# AD9837MagPhase.net
KiCad netlist of a schematic drawn in Altium Designer
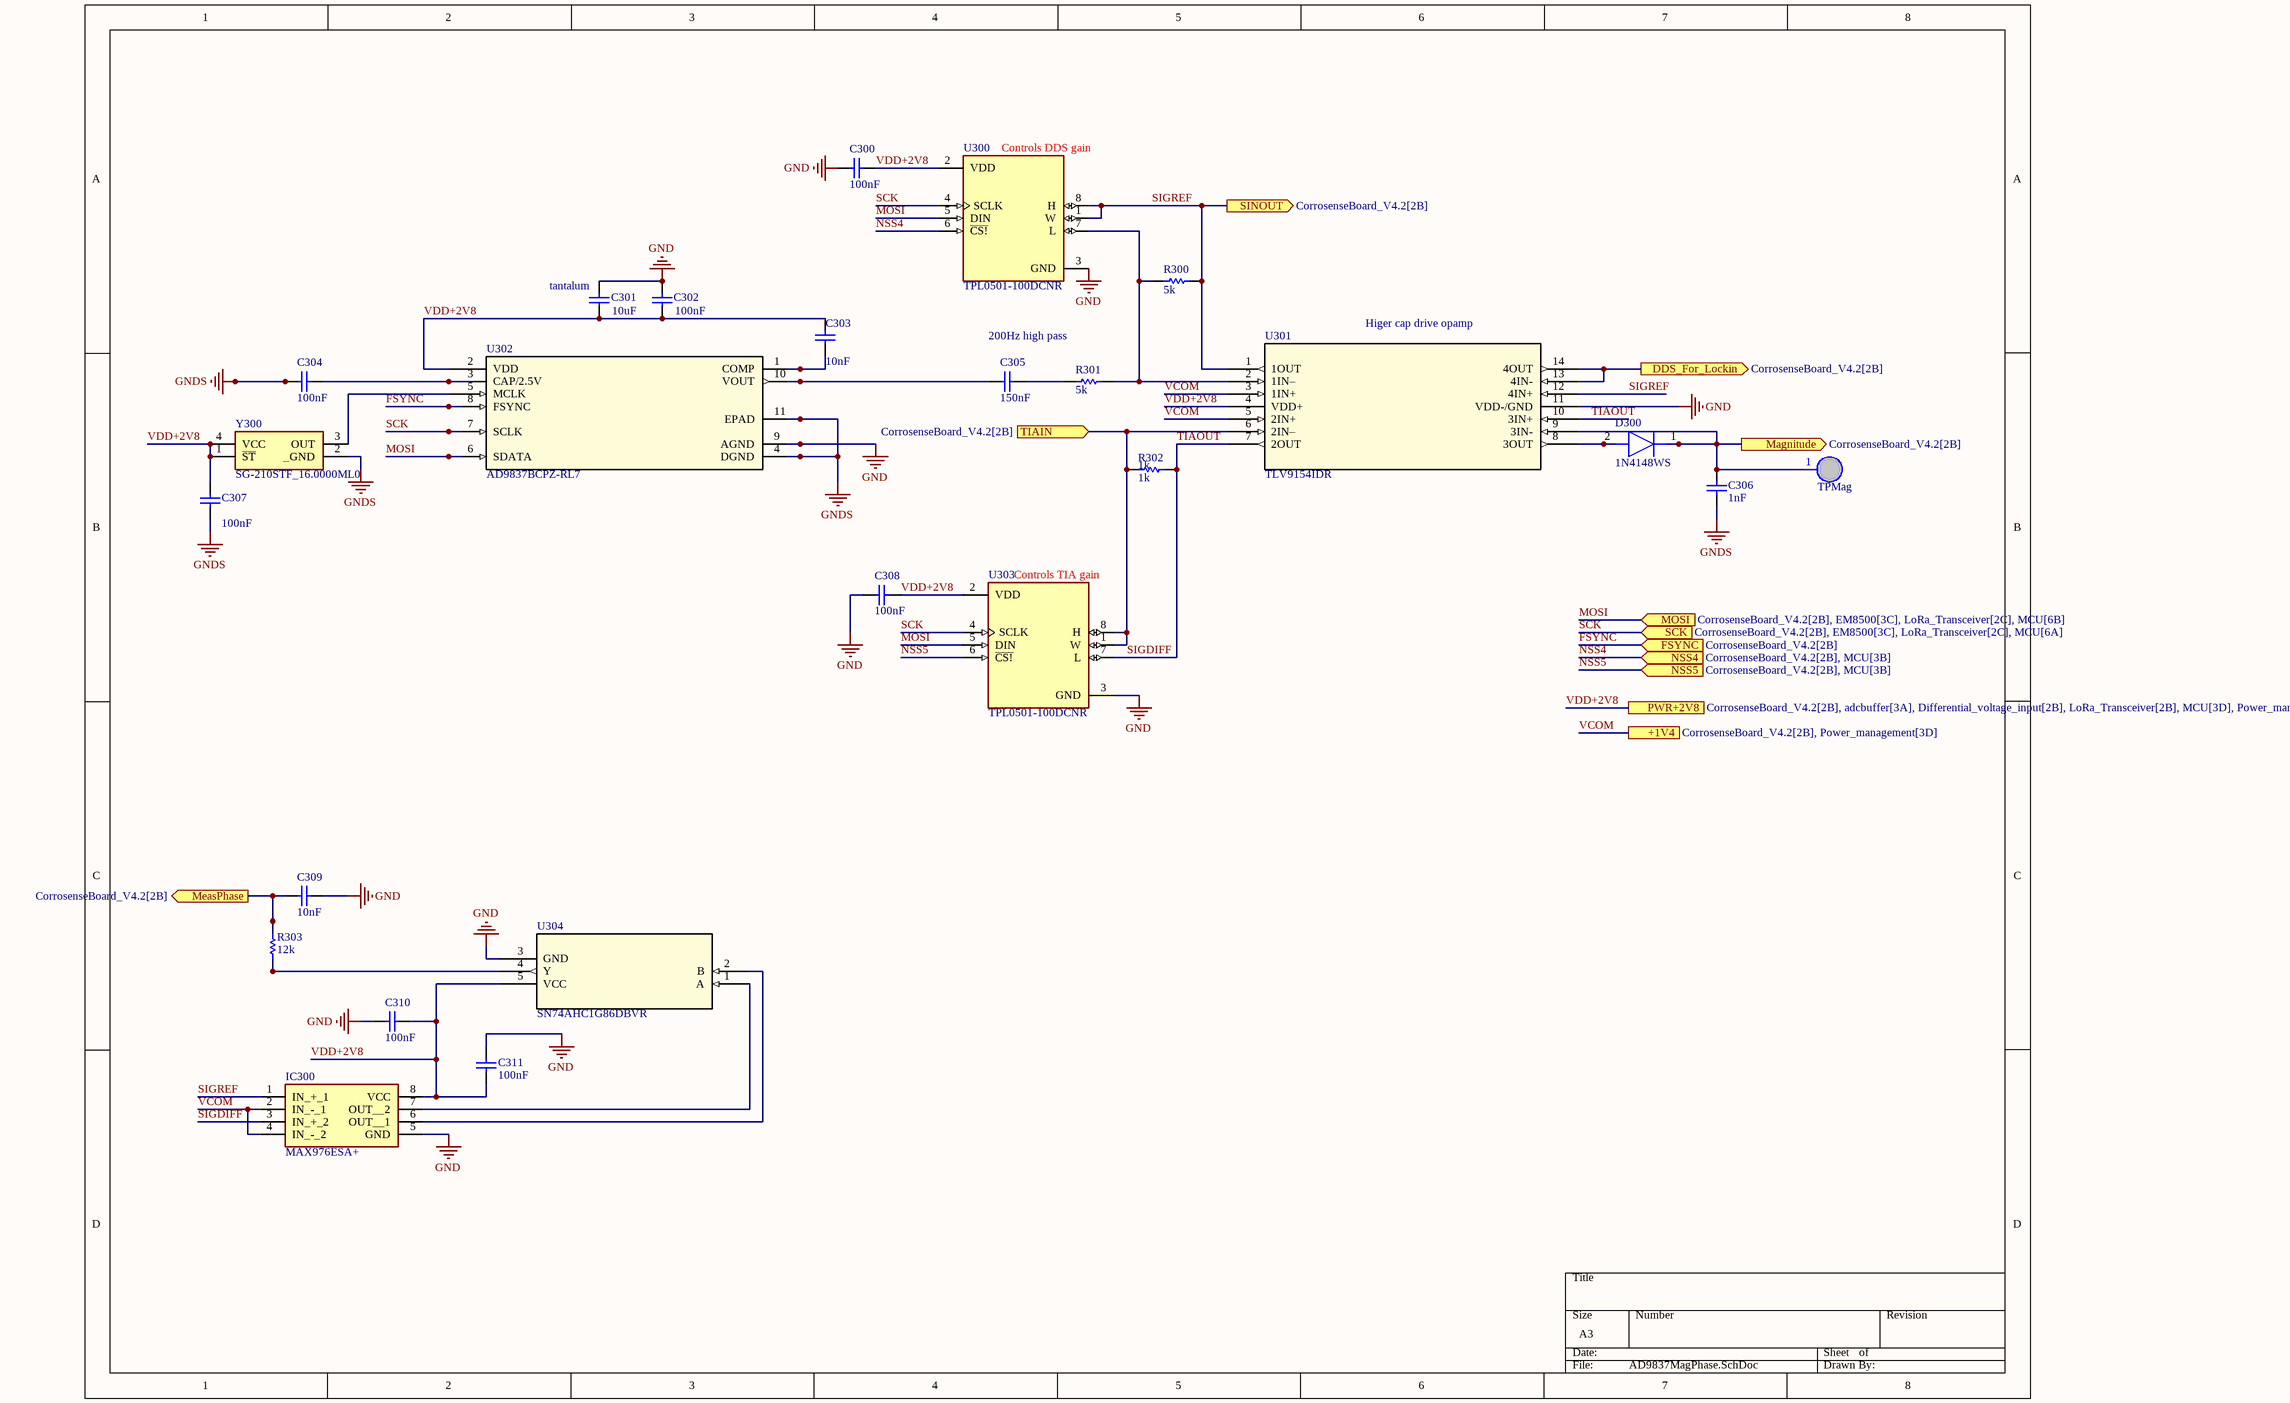
[diagram p0: AD9837MagPhase.SchDoc]

(export (version "E")
  (design (tool "Eeschema 10.0.6"))
  (components
    (comp (ref "C300")
      (value "100nF")
      (footprint "1608[0603]")
      (description "CAP CER 25V X7R 0603")
      (fields (field (name "TOLERANCE") "±10%") (field (name "MANUFACTURER") "Murata Electronics"))
      (libsource (lib "Miscellaneous Devices") (part "Cap"))
    )
    (comp (ref "C301")
      (value "10uF")
      (footprint "1608[0603]")
      (description "CAP CER 25V X7R 0603")
      (fields (field (name "TOLERANCE") "±20%") (field (name "MANUFACTURER") "Vishay / Sprague"))
      (libsource (lib "Miscellaneous Devices") (part "Cap"))
    )
    (comp (ref "C302")
      (value "100nF")
      (footprint "1608[0603]")
      (description "CAP CER 25V X7R 0603")
      (fields (field (name "TOLERANCE") "±10%") (field (name "MANUFACTURER") "Murata Electronics"))
      (libsource (lib "Miscellaneous Devices") (part "Cap"))
    )
    (comp (ref "C303")
      (value "10nF")
      (footprint "1608[0603]")
      (description "CAP CER 25V X7R 0603")
      (fields (field (name "TOLERANCE") "±10%") (field (name "MANUFACTURER") "Murata Electronics"))
      (libsource (lib "Miscellaneous Devices") (part "Cap"))
    )
    (comp (ref "C304")
      (value "100nF")
      (footprint "1608[0603]")
      (description "CAP CER 25V X7R 0603")
      (fields (field (name "TOLERANCE") "±10%") (field (name "MANUFACTURER") "Murata Electronics"))
      (libsource (lib "Miscellaneous Devices") (part "Cap"))
    )
    (comp (ref "C305")
      (value "150nF")
      (footprint "1608[0603]")
      (description "CAP CER 25V X7R 0603")
      (fields (field (name "TOLERANCE") "±10%") (field (name "MANUFACTURER") "Murata Electronics"))
      (libsource (lib "Miscellaneous Devices") (part "Cap"))
    )
    (comp (ref "C306")
      (value "1nF")
      (footprint "1608[0603]")
      (description "CAP CER 25V X7R 0603")
      (fields (field (name "TOLERANCE") "±10%") (field (name "MANUFACTURER") "KYOCERA AVX"))
      (libsource (lib "Miscellaneous Devices") (part "Cap"))
    )
    (comp (ref "C307")
      (value "100nF")
      (footprint "1608[0603]")
      (description "CAP CER 25V X7R 0603")
      (fields (field (name "TOLERANCE") "±10%") (field (name "MANUFACTURER") "Murata Electronics"))
      (libsource (lib "Miscellaneous Devices") (part "Cap"))
    )
    (comp (ref "C308")
      (value "100nF")
      (footprint "1608[0603]")
      (description "CAP CER 25V X7R 0603")
      (fields (field (name "TOLERANCE") "±10%") (field (name "MANUFACTURER") "Murata Electronics"))
      (libsource (lib "Miscellaneous Devices") (part "Cap"))
    )
    (comp (ref "C309")
      (value "10nF")
      (footprint "1608[0603]")
      (description "CAP CER 25V X7R 0603")
      (fields (field (name "TOLERANCE") "±10%") (field (name "MANUFACTURER") "Murata Electronics"))
      (libsource (lib "Miscellaneous Devices") (part "Cap"))
    )
    (comp (ref "C310")
      (value "100nF")
      (footprint "1608[0603]")
      (description "CAP CER 25V X7R 0603")
      (fields (field (name "TOLERANCE") "±10%") (field (name "MANUFACTURER") "Murata Electronics"))
      (libsource (lib "Miscellaneous Devices") (part "Cap"))
    )
    (comp (ref "C311")
      (value "100nF")
      (footprint "1608[0603]")
      (description "CAP CER 25V X7R 0603")
      (fields (field (name "TOLERANCE") "±10%") (field (name "MANUFACTURER") "Murata Electronics"))
      (libsource (lib "Miscellaneous Devices") (part "Cap"))
    )
    (comp (ref "D300")
      (value "1N4148WS")
      (footprint "SamacSys:SOD2513X100N")
      (description "Diode")
      (fields
        (field (name "MOUSER PART NUMBER") "821-1N4148WS")
        (field (name "MANUFACTURER") "Taiwan Semiconductor")
      )
      (libsource (lib "*") (part "1N4148WS"))
    )
    (comp (ref "IC300")
      (value "MAX976ESA+")
      (footprint "SOIC127P600X175-8N")
      (description "Integrated Circuit")
      (fields
        (field (name "MOUSER PART NUMBER") "700-MAX976ESA")
        (field (name "MANUFACTURER") "Analog Devices")
      )
      (libsource (lib "*") (part "MAX976ESA+"))
    )
    (comp (ref "R300")
      (value "5k")
      (footprint "1608[0603]")
      (description "RES SMD 2% 1.5W 0603")
      (fields
        (field (name "MP") "-65°C ~ 155°C")
        (field (name "TOLERANCE") "2%")
        (field (name "PUBLISHER") "Altium Limited")
      )
      (libsource (lib "Res1") (part "Res1"))
    )
    (comp (ref "R301")
      (value "5k")
      (footprint "1608[0603]")
      (description "RES SMD 2% 1.5W 0603")
      (fields
        (field (name "MP") "-65°C ~ 155°C")
        (field (name "TOLERANCE") "2%")
        (field (name "PUBLISHER") "Altium Limited")
      )
      (libsource (lib "Res1") (part "Res1"))
    )
    (comp (ref "R302")
      (value "1k")
      (footprint "1608[0603]")
      (description "RES SMD 2% 1.5W 0603")
      (fields
        (field (name "ALTIUM_VALUE") "1k")
        (field (name "MP") "-65°C ~ 155°C")
        (field (name "TOLERANCE") "2%")
        (field (name "PUBLISHER") "Altium Limited")
      )
      (libsource (lib "Res1") (part "Res1"))
    )
    (comp (ref "R303")
      (value "12k")
      (footprint "1608[0603]")
      (description "RES SMD 2% 1.5W 0603")
      (fields
        (field (name "MP") "-65°C ~ 155°C")
        (field (name "TOLERANCE") "2%")
        (field (name "PUBLISHER") "Altium Limited")
      )
      (libsource (lib "Res1") (part "Res1"))
    )
    (comp (ref "TPMag") (value "TP") (footprint "PCBComponent_1") (libsource (lib "TP") (part "TP")))
    (comp (ref "U300")
      (value "TPL0501-100DCNR")
      (footprint "SOT65P280X145-8N")
      (description "256-Taps, 100k, Single-Channel Potentiometer With SPI Interface 8-SOT-23 -40 to 125")
      (fields (field (name "MANUFACTURER") "Texas Instruments"))
      (libsource (lib "TPL0501-100DCNR") (part "TPL0501-100DCNR"))
    )
    (comp (ref "U301")
      (value "TLV9154IDR")
      (footprint "SOIC127P600X175-14N")
      (description "No Description Available")
      (fields (field (name "MANUFACTURER") "Texas Instruments"))
      (libsource (lib "TLV2444CD") (part "TLV2444CD"))
    )
    (comp (ref "U302")
      (value "AD9837BCPZ-RL7")
      (footprint "CP_10_9_ADI")
      (description "No Description Available")
      (fields (field (name "MANUFACTURER") "Analog Devices"))
      (libsource (lib "AD9837ACPZ-RL7") (part "AD9837ACPZ-RL7"))
    )
    (comp (ref "U303")
      (value "TPL0501-100DCNR")
      (footprint "SOT65P280X145-8N")
      (description "256-Taps, 100k, Single-Channel Potentiometer With SPI Interface 8-SOT-23 -40 to 125")
      (fields (field (name "MANUFACTURER") "Texas Instruments"))
      (libsource (lib "TPL0501-100DCNR") (part "TPL0501-100DCNR"))
    )
    (comp (ref "U304")
      (value "SN74AHC1G86DBVR")
      (footprint "SOT95P280X145-5N")
      (description "No Description Available")
      (fields (field (name "MANUFACTURER") "Texas Instruments"))
      (libsource (lib "SN74AHC1G86DBVR") (part "SN74AHC1G86DBVR"))
    )
    (comp (ref "Y300")
      (value "SG-210STF_16.0000ML0")
      (footprint "SG210STF160000ML0")
      (description "Crystal or Oscillator")
      (fields
        (field (name "MANUFACTURER_PART_NUMBER") "SG-210STF 16.0000ML0")
        (field (name "MOUSER PART NUMBER") "732-SG-210STF16ML0")
      )
      (libsource (lib "*") (part "SG-210STF_16.0000ML0"))
    )
  )
  (nets
    (net (code "1") (name "/DDS_For_Lockin") (class "Default")
      (node (ref "U301") (pin "13") (pinfunction "4IN-_13") (pintype "input"))
      (node (ref "U301") (pin "14") (pinfunction "4OUT_14") (pintype "output"))
    )
    (net (code "2") (name "/FSYNC") (class "Default")
      (node (ref "U302") (pin "8") (pinfunction "FSYNC_8") (pintype "input"))
    )
    (net (code "3") (name "/MOSI") (class "Default")
      (node (ref "U300") (pin "5") (pinfunction "DIN_5") (pintype "input"))
      (node (ref "U302") (pin "6") (pinfunction "SDATA_6") (pintype "input"))
      (node (ref "U303") (pin "5") (pinfunction "DIN_5") (pintype "input"))
    )
    (net (code "4") (name "/Magnitude") (class "Default")
      (node (ref "C306") (pin "1") (pinfunction "1_1") (pintype "passive"))
      (node (ref "D300") (pin "1") (pinfunction "K_1") (pintype "passive"))
      (node (ref "TPMag") (pin "1") (pinfunction "6_1") (pintype "passive"))
      (node (ref "U301") (pin "9") (pinfunction "3IN-_9") (pintype "input"))
    )
    (net (code "5") (name "/MeasPhase") (class "Default")
      (node (ref "C309") (pin "1") (pinfunction "1_1") (pintype "passive"))
      (node (ref "R303") (pin "2") (pinfunction "2_2") (pintype "passive"))
    )
    (net (code "6") (name "/NSS4") (class "Default")
      (node (ref "U300") (pin "6") (pinfunction "~{CS!}_6") (pintype "input"))
    )
    (net (code "7") (name "/NSS5") (class "Default")
      (node (ref "U303") (pin "6") (pinfunction "~{CS!}_6") (pintype "input"))
    )
    (net (code "8") (name "/SCK") (class "Default")
      (node (ref "U300") (pin "4") (pinfunction "SCLK_4") (pintype "input"))
      (node (ref "U302") (pin "7") (pinfunction "SCLK_7") (pintype "input"))
      (node (ref "U303") (pin "4") (pinfunction "SCLK_4") (pintype "input"))
    )
    (net (code "9") (name "/SIGDIFF") (class "Default")
      (node (ref "IC300") (pin "3") (pinfunction "IN_+_2_3") (pintype "passive"))
      (node (ref "R302") (pin "1") (pinfunction "1_1") (pintype "passive"))
      (node (ref "U301") (pin "10") (pinfunction "3IN+_10") (pintype "input"))
      (node (ref "U301") (pin "7") (pinfunction "2OUT_7") (pintype "output"))
      (node (ref "U303") (pin "7") (pinfunction "L_7") (pintype "bidirectional"))
    )
    (net (code "10") (name "/SIGREF") (class "Default")
      (node (ref "IC300") (pin "1") (pinfunction "IN_+_1_1") (pintype "passive"))
      (node (ref "R300") (pin "1") (pinfunction "1_1") (pintype "passive"))
      (node (ref "U300") (pin "1") (pinfunction "W_1") (pintype "bidirectional"))
      (node (ref "U300") (pin "8") (pinfunction "H_8") (pintype "bidirectional"))
      (node (ref "U301") (pin "1") (pinfunction "1OUT_1") (pintype "output"))
      (node (ref "U301") (pin "12") (pinfunction "4IN+_12") (pintype "input"))
    )
    (net (code "11") (name "/TIAIN") (class "Default")
      (node (ref "R302") (pin "2") (pinfunction "2_2") (pintype "passive"))
      (node (ref "U301") (pin "6") (pinfunction "2IN–_6") (pintype "input"))
      (node (ref "U303") (pin "1") (pinfunction "W_1") (pintype "bidirectional"))
      (node (ref "U303") (pin "8") (pinfunction "H_8") (pintype "bidirectional"))
    )
    (net (code "12") (name "/VCOM") (class "Default")
      (node (ref "IC300") (pin "2") (pinfunction "IN_-_1_2") (pintype "passive"))
      (node (ref "IC300") (pin "4") (pinfunction "IN_-_2_4") (pintype "passive"))
      (node (ref "U301") (pin "3") (pinfunction "1IN+_3") (pintype "input"))
      (node (ref "U301") (pin "5") (pinfunction "2IN+_5") (pintype "input"))
    )
    (net (code "13") (name "/VDD+2V8") (class "Default")
      (node (ref "C300") (pin "1") (pinfunction "1_1") (pintype "passive"))
      (node (ref "C301") (pin "1") (pinfunction "1_1") (pintype "passive"))
      (node (ref "C302") (pin "1") (pinfunction "1_1") (pintype "passive"))
      (node (ref "C303") (pin "2") (pinfunction "2_2") (pintype "passive"))
      (node (ref "C307") (pin "2") (pinfunction "2_2") (pintype "passive"))
      (node (ref "C308") (pin "1") (pinfunction "1_1") (pintype "passive"))
      (node (ref "C310") (pin "1") (pinfunction "1_1") (pintype "passive"))
      (node (ref "C311") (pin "2") (pinfunction "2_2") (pintype "passive"))
      (node (ref "IC300") (pin "8") (pinfunction "VCC_8") (pintype "passive"))
      (node (ref "U300") (pin "2") (pinfunction "VDD_2") (pintype "power_in"))
      (node (ref "U301") (pin "4") (pinfunction "VDD+_4") (pintype "power_in"))
      (node (ref "U302") (pin "2") (pinfunction "VDD_2") (pintype "power_in"))
      (node (ref "U303") (pin "2") (pinfunction "VDD_2") (pintype "power_in"))
      (node (ref "U304") (pin "5") (pinfunction "VCC_5") (pintype "power_in"))
      (node (ref "Y300") (pin "1") (pinfunction "~{ST}_1") (pintype "passive"))
      (node (ref "Y300") (pin "4") (pinfunction "VCC_4") (pintype "passive"))
    )
    (net (code "14") (name "GND") (class "Default")
      (node (ref "C300") (pin "2") (pinfunction "2_2") (pintype "passive"))
      (node (ref "C301") (pin "2") (pinfunction "2_2") (pintype "passive"))
      (node (ref "C302") (pin "2") (pinfunction "2_2") (pintype "passive"))
      (node (ref "C308") (pin "2") (pinfunction "2_2") (pintype "passive"))
      (node (ref "C309") (pin "2") (pinfunction "2_2") (pintype "passive"))
      (node (ref "C310") (pin "2") (pinfunction "2_2") (pintype "passive"))
      (node (ref "C311") (pin "1") (pinfunction "1_1") (pintype "passive"))
      (node (ref "IC300") (pin "5") (pinfunction "GND_5") (pintype "passive"))
      (node (ref "U300") (pin "3") (pinfunction "GND_3") (pintype "power_in"))
      (node (ref "U301") (pin "11") (pinfunction "VDD-/GND_11") (pintype "power_in"))
      (node (ref "U302") (pin "9") (pinfunction "AGND_9") (pintype "power_in"))
      (node (ref "U303") (pin "3") (pinfunction "GND_3") (pintype "power_in"))
      (node (ref "U304") (pin "3") (pinfunction "GND_3") (pintype "power_in"))
    )
    (net (code "15") (name "GNDS") (class "Default")
      (node (ref "C304") (pin "2") (pinfunction "2_2") (pintype "passive"))
      (node (ref "C306") (pin "2") (pinfunction "2_2") (pintype "passive"))
      (node (ref "C307") (pin "1") (pinfunction "1_1") (pintype "passive"))
      (node (ref "U302") (pin "11") (pinfunction "EPAD_11") (pintype "passive"))
      (node (ref "U302") (pin "4") (pinfunction "DGND_4") (pintype "power_in"))
      (node (ref "Y300") (pin "2") (pinfunction "_GND_2") (pintype "passive"))
    )
    (net (code "16") (name "Net-(C305-Pad1)") (class "Default")
      (node (ref "C305") (pin "1") (pinfunction "1_1") (pintype "passive"))
      (node (ref "R301") (pin "2") (pinfunction "2_2") (pintype "passive"))
    )
    (net (code "17") (name "Net-(D300-A)") (class "Default")
      (node (ref "D300") (pin "2") (pinfunction "A_2") (pintype "passive"))
      (node (ref "U301") (pin "8") (pinfunction "3OUT_8") (pintype "output"))
    )
    (net (code "18") (name "Net-(IC300-OUT__1)") (class "Default")
      (node (ref "IC300") (pin "6") (pinfunction "OUT__1_6") (pintype "passive"))
      (node (ref "U304") (pin "2") (pinfunction "B_2") (pintype "input"))
    )
    (net (code "19") (name "Net-(IC300-OUT__2)") (class "Default")
      (node (ref "IC300") (pin "7") (pinfunction "OUT__2_7") (pintype "passive"))
      (node (ref "U304") (pin "1") (pinfunction "A_1") (pintype "input"))
    )
    (net (code "20") (name "Net-(U300-L)") (class "Default")
      (node (ref "R300") (pin "2") (pinfunction "2_2") (pintype "passive"))
      (node (ref "R301") (pin "1") (pinfunction "1_1") (pintype "passive"))
      (node (ref "U300") (pin "7") (pinfunction "L_7") (pintype "bidirectional"))
      (node (ref "U301") (pin "2") (pinfunction "1IN–_2") (pintype "input"))
    )
    (net (code "21") (name "Net-(U302-CAP{slash}2.5V)") (class "Default")
      (node (ref "C304") (pin "1") (pinfunction "1_1") (pintype "passive"))
      (node (ref "U302") (pin "3") (pinfunction "CAP/2.5V_3") (pintype "passive"))
    )
    (net (code "22") (name "Net-(U302-COMP)") (class "Default")
      (node (ref "C303") (pin "1") (pinfunction "1_1") (pintype "passive"))
      (node (ref "U302") (pin "1") (pinfunction "COMP_1") (pintype "passive"))
    )
    (net (code "23") (name "Net-(U302-MCLK)") (class "Default")
      (node (ref "U302") (pin "5") (pinfunction "MCLK_5") (pintype "input"))
      (node (ref "Y300") (pin "3") (pinfunction "OUT_3") (pintype "passive"))
    )
    (net (code "24") (name "Net-(U302-VOUT)") (class "Default")
      (node (ref "C305") (pin "2") (pinfunction "2_2") (pintype "passive"))
      (node (ref "U302") (pin "10") (pinfunction "VOUT_10") (pintype "output"))
    )
    (net (code "25") (name "Net-(U304-Y)") (class "Default")
      (node (ref "R303") (pin "1") (pinfunction "1_1") (pintype "passive"))
      (node (ref "U304") (pin "4") (pinfunction "Y_4") (pintype "output"))
    )
  )
)
